# Current_Detection_1_8.net
KiCad netlist of a schematic drawn in Altium Designer
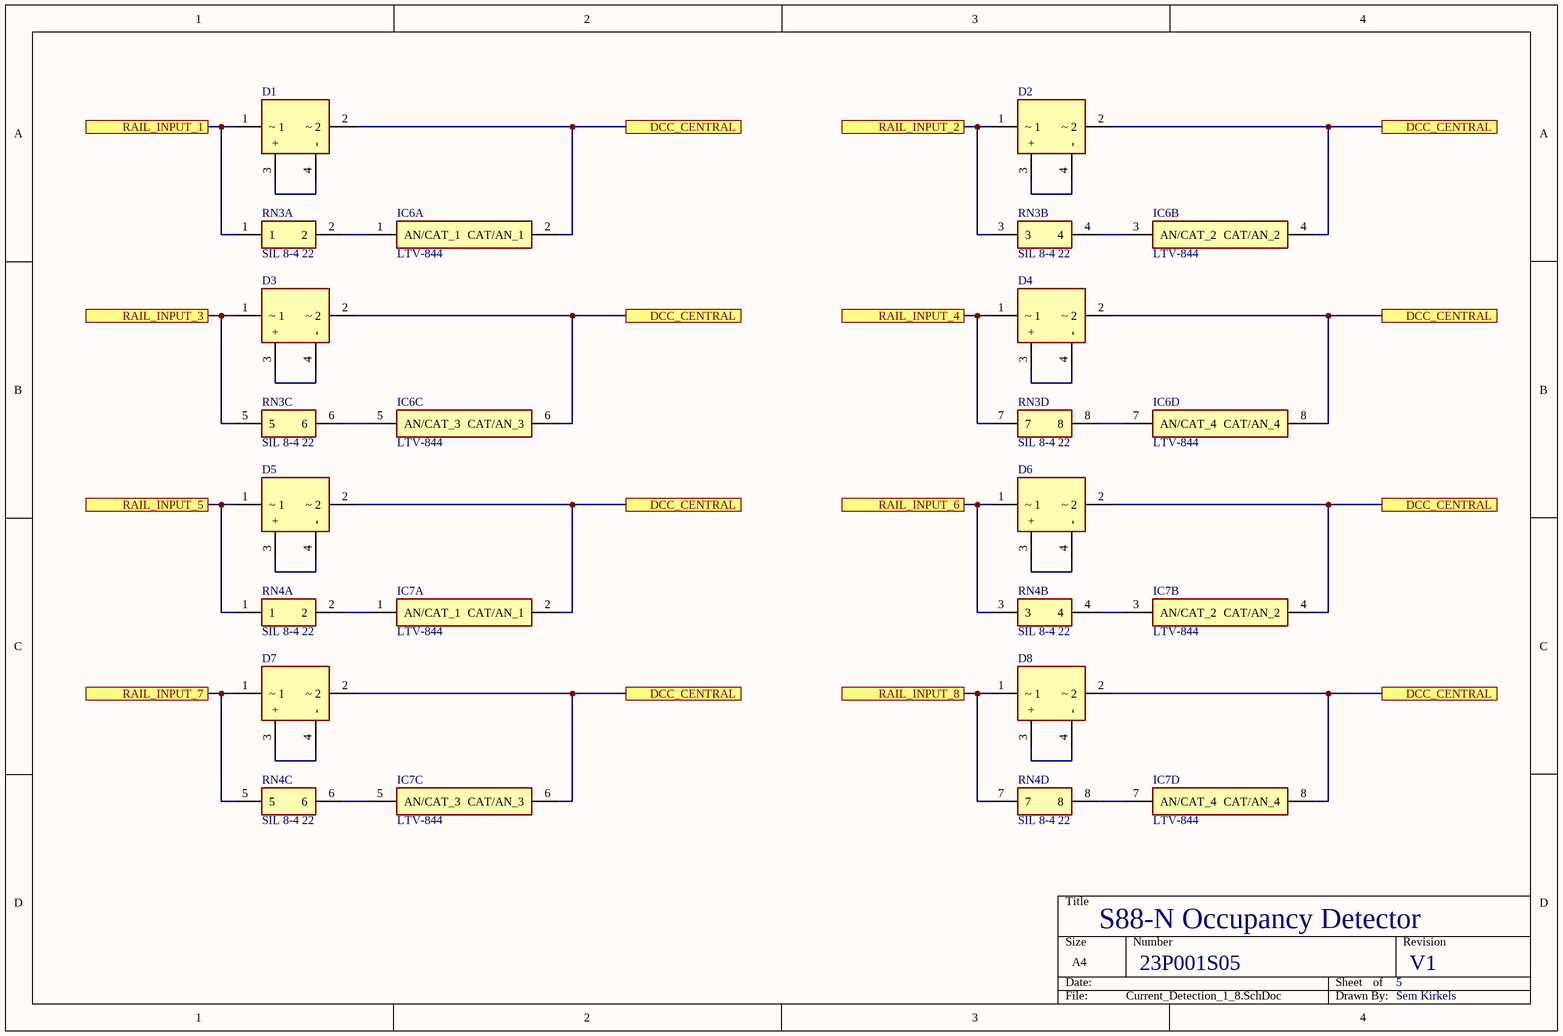
[diagram p0: Current_Detection_1_8.SchDoc]

(export (version "E")
  (design (tool "Eeschema 10.0.6"))
  (components
    (comp (ref "D1")
      (value "B140C1000DIP_DB101")
      (footprint "FBR_B140C1000DIP")
      (description "Bridge Rectifier")
      (fields
        (field (name "MANUFACTURER_PART_NUMBER") "DB101")
        (field (name "MOUSER PART NUMBER") "583-DB101")
      )
      (libsource (lib "Schematic_Library_S88N") (part "B140C1000DIP_DB101"))
    )
    (comp (ref "D2")
      (value "B140C1000DIP_DB101")
      (footprint "FBR_B140C1000DIP")
      (description "Bridge Rectifier")
      (fields
        (field (name "MANUFACTURER_PART_NUMBER") "DB101")
        (field (name "MOUSER PART NUMBER") "583-DB101")
      )
      (libsource (lib "Schematic_Library_S88N") (part "B140C1000DIP_DB101"))
    )
    (comp (ref "D3")
      (value "B140C1000DIP_DB101")
      (footprint "FBR_B140C1000DIP")
      (description "Bridge Rectifier")
      (fields
        (field (name "MANUFACTURER_PART_NUMBER") "DB101")
        (field (name "MOUSER PART NUMBER") "583-DB101")
      )
      (libsource (lib "Schematic_Library_S88N") (part "B140C1000DIP_DB101"))
    )
    (comp (ref "D4")
      (value "B140C1000DIP_DB101")
      (footprint "FBR_B140C1000DIP")
      (description "Bridge Rectifier")
      (fields
        (field (name "MANUFACTURER_PART_NUMBER") "DB101")
        (field (name "MOUSER PART NUMBER") "583-DB101")
      )
      (libsource (lib "Schematic_Library_S88N") (part "B140C1000DIP_DB101"))
    )
    (comp (ref "D5")
      (value "B140C1000DIP_DB101")
      (footprint "FBR_B140C1000DIP")
      (description "Bridge Rectifier")
      (fields
        (field (name "MANUFACTURER_PART_NUMBER") "DB101")
        (field (name "MOUSER PART NUMBER") "583-DB101")
      )
      (libsource (lib "Schematic_Library_S88N") (part "B140C1000DIP_DB101"))
    )
    (comp (ref "D6")
      (value "B140C1000DIP_DB101")
      (footprint "FBR_B140C1000DIP")
      (description "Bridge Rectifier")
      (fields
        (field (name "MANUFACTURER_PART_NUMBER") "DB101")
        (field (name "MOUSER PART NUMBER") "583-DB101")
      )
      (libsource (lib "Schematic_Library_S88N") (part "B140C1000DIP_DB101"))
    )
    (comp (ref "D7")
      (value "B140C1000DIP_DB101")
      (footprint "FBR_B140C1000DIP")
      (description "Bridge Rectifier")
      (fields
        (field (name "MANUFACTURER_PART_NUMBER") "DB101")
        (field (name "MOUSER PART NUMBER") "583-DB101")
      )
      (libsource (lib "Schematic_Library_S88N") (part "B140C1000DIP_DB101"))
    )
    (comp (ref "D8")
      (value "B140C1000DIP_DB101")
      (footprint "FBR_B140C1000DIP")
      (description "Bridge Rectifier")
      (fields
        (field (name "MANUFACTURER_PART_NUMBER") "DB101")
        (field (name "MOUSER PART NUMBER") "583-DB101")
      )
      (libsource (lib "Schematic_Library_S88N") (part "B140C1000DIP_DB101"))
    )
    (comp (ref "IC6")
      (value "LTV-844")
      (footprint "CD4014")
      (description "Integrated Circuit")
      (fields (field (name "MOUSER PART NUMBER") "859-LTV-844"))
      (libsource (lib "Schematic_Library_S88N") (part "LTV-844"))
    )
    (comp (ref "IC7")
      (value "LTV-844")
      (footprint "CD4014")
      (description "Integrated Circuit")
      (fields (field (name "MOUSER PART NUMBER") "859-LTV-844"))
      (libsource (lib "Schematic_Library_S88N") (part "LTV-844"))
    )
    (comp (ref "RN3")
      (value "SIL 8-4 22")
      (footprint "SIL 8-4")
      (description "Resistor Network")
      (fields
        (field (name "MANUFACTURER_PART_NUMBER") "4608X-102-102LF")
        (field (name "MOUSER PART NUMBER") "652-4608X-2LF-1K")
      )
      (libsource (lib "Schematic_Library_S88N") (part "SIL 8-4 22"))
    )
    (comp (ref "RN4")
      (value "SIL 8-4 22")
      (footprint "SIL 8-4")
      (description "Resistor Network")
      (fields
        (field (name "MANUFACTURER_PART_NUMBER") "4608X-102-102LF")
        (field (name "MOUSER PART NUMBER") "652-4608X-2LF-1K")
      )
      (libsource (lib "Schematic_Library_S88N") (part "SIL 8-4 22"))
    )
  )
  (nets
    (net (code "1") (name "/DCC_CENTRAL") (class "Default")
      (node (ref "D1") (pin "2") (pinfunction "~_2_2") (pintype "passive"))
      (node (ref "D2") (pin "2") (pinfunction "~_2_2") (pintype "passive"))
      (node (ref "D3") (pin "2") (pinfunction "~_2_2") (pintype "passive"))
      (node (ref "D4") (pin "2") (pinfunction "~_2_2") (pintype "passive"))
      (node (ref "D5") (pin "2") (pinfunction "~_2_2") (pintype "passive"))
      (node (ref "D6") (pin "2") (pinfunction "~_2_2") (pintype "passive"))
      (node (ref "D7") (pin "2") (pinfunction "~_2_2") (pintype "passive"))
      (node (ref "D8") (pin "2") (pinfunction "~_2_2") (pintype "passive"))
      (node (ref "IC6") (pin "2") (pinfunction "CAT/AN_1_2") (pintype "passive"))
      (node (ref "IC6") (pin "4") (pinfunction "CAT/AN_2_4") (pintype "passive"))
      (node (ref "IC6") (pin "6") (pinfunction "CAT/AN_3_6") (pintype "passive"))
      (node (ref "IC6") (pin "8") (pinfunction "CAT/AN_4_8") (pintype "passive"))
      (node (ref "IC7") (pin "2") (pinfunction "CAT/AN_1_2") (pintype "passive"))
      (node (ref "IC7") (pin "4") (pinfunction "CAT/AN_2_4") (pintype "passive"))
      (node (ref "IC7") (pin "6") (pinfunction "CAT/AN_3_6") (pintype "passive"))
      (node (ref "IC7") (pin "8") (pinfunction "CAT/AN_4_8") (pintype "passive"))
    )
    (net (code "2") (name "/RAIL_INPUT_1") (class "Default")
      (node (ref "D1") (pin "1") (pinfunction "~_1_1") (pintype "passive"))
      (node (ref "RN3") (pin "1") (pinfunction "1_1") (pintype "passive"))
    )
    (net (code "3") (name "/RAIL_INPUT_2") (class "Default")
      (node (ref "D2") (pin "1") (pinfunction "~_1_1") (pintype "passive"))
      (node (ref "RN3") (pin "3") (pinfunction "3_3") (pintype "passive"))
    )
    (net (code "4") (name "/RAIL_INPUT_3") (class "Default")
      (node (ref "D3") (pin "1") (pinfunction "~_1_1") (pintype "passive"))
      (node (ref "RN3") (pin "5") (pinfunction "5_5") (pintype "passive"))
    )
    (net (code "5") (name "/RAIL_INPUT_4") (class "Default")
      (node (ref "D4") (pin "1") (pinfunction "~_1_1") (pintype "passive"))
      (node (ref "RN3") (pin "7") (pinfunction "7_7") (pintype "passive"))
    )
    (net (code "6") (name "/RAIL_INPUT_5") (class "Default")
      (node (ref "D5") (pin "1") (pinfunction "~_1_1") (pintype "passive"))
      (node (ref "RN4") (pin "1") (pinfunction "1_1") (pintype "passive"))
    )
    (net (code "7") (name "/RAIL_INPUT_6") (class "Default")
      (node (ref "D6") (pin "1") (pinfunction "~_1_1") (pintype "passive"))
      (node (ref "RN4") (pin "3") (pinfunction "3_3") (pintype "passive"))
    )
    (net (code "8") (name "/RAIL_INPUT_7") (class "Default")
      (node (ref "D7") (pin "1") (pinfunction "~_1_1") (pintype "passive"))
      (node (ref "RN4") (pin "5") (pinfunction "5_5") (pintype "passive"))
    )
    (net (code "9") (name "/RAIL_INPUT_8") (class "Default")
      (node (ref "D8") (pin "1") (pinfunction "~_1_1") (pintype "passive"))
      (node (ref "RN4") (pin "7") (pinfunction "7_7") (pintype "passive"))
    )
    (net (code "10") (name "Net-(D1-+)") (class "Default")
      (node (ref "D1") (pin "3") (pinfunction "+_3") (pintype "passive"))
      (node (ref "D1") (pin "4") (pinfunction "-_4") (pintype "passive"))
    )
    (net (code "11") (name "Net-(D2-+)") (class "Default")
      (node (ref "D2") (pin "3") (pinfunction "+_3") (pintype "passive"))
      (node (ref "D2") (pin "4") (pinfunction "-_4") (pintype "passive"))
    )
    (net (code "12") (name "Net-(D3-+)") (class "Default")
      (node (ref "D3") (pin "3") (pinfunction "+_3") (pintype "passive"))
      (node (ref "D3") (pin "4") (pinfunction "-_4") (pintype "passive"))
    )
    (net (code "13") (name "Net-(D4-+)") (class "Default")
      (node (ref "D4") (pin "3") (pinfunction "+_3") (pintype "passive"))
      (node (ref "D4") (pin "4") (pinfunction "-_4") (pintype "passive"))
    )
    (net (code "14") (name "Net-(D5-+)") (class "Default")
      (node (ref "D5") (pin "3") (pinfunction "+_3") (pintype "passive"))
      (node (ref "D5") (pin "4") (pinfunction "-_4") (pintype "passive"))
    )
    (net (code "15") (name "Net-(D6-+)") (class "Default")
      (node (ref "D6") (pin "3") (pinfunction "+_3") (pintype "passive"))
      (node (ref "D6") (pin "4") (pinfunction "-_4") (pintype "passive"))
    )
    (net (code "16") (name "Net-(D7-+)") (class "Default")
      (node (ref "D7") (pin "3") (pinfunction "+_3") (pintype "passive"))
      (node (ref "D7") (pin "4") (pinfunction "-_4") (pintype "passive"))
    )
    (net (code "17") (name "Net-(D8-+)") (class "Default")
      (node (ref "D8") (pin "3") (pinfunction "+_3") (pintype "passive"))
      (node (ref "D8") (pin "4") (pinfunction "-_4") (pintype "passive"))
    )
    (net (code "18") (name "Net-(IC6A-AN{slash}CAT_1)") (class "Default")
      (node (ref "IC6") (pin "1") (pinfunction "AN/CAT_1_1") (pintype "passive"))
      (node (ref "RN3") (pin "2") (pinfunction "2_2") (pintype "passive"))
    )
    (net (code "19") (name "Net-(IC6B-AN{slash}CAT_2)") (class "Default")
      (node (ref "IC6") (pin "3") (pinfunction "AN/CAT_2_3") (pintype "passive"))
      (node (ref "RN3") (pin "4") (pinfunction "4_4") (pintype "passive"))
    )
    (net (code "20") (name "Net-(IC6C-AN{slash}CAT_3)") (class "Default")
      (node (ref "IC6") (pin "5") (pinfunction "AN/CAT_3_5") (pintype "passive"))
      (node (ref "RN3") (pin "6") (pinfunction "6_6") (pintype "passive"))
    )
    (net (code "21") (name "Net-(IC6D-AN{slash}CAT_4)") (class "Default")
      (node (ref "IC6") (pin "7") (pinfunction "AN/CAT_4_7") (pintype "passive"))
      (node (ref "RN3") (pin "8") (pinfunction "8_8") (pintype "passive"))
    )
    (net (code "22") (name "Net-(IC7A-AN{slash}CAT_1)") (class "Default")
      (node (ref "IC7") (pin "1") (pinfunction "AN/CAT_1_1") (pintype "passive"))
      (node (ref "RN4") (pin "2") (pinfunction "2_2") (pintype "passive"))
    )
    (net (code "23") (name "Net-(IC7B-AN{slash}CAT_2)") (class "Default")
      (node (ref "IC7") (pin "3") (pinfunction "AN/CAT_2_3") (pintype "passive"))
      (node (ref "RN4") (pin "4") (pinfunction "4_4") (pintype "passive"))
    )
    (net (code "24") (name "Net-(IC7C-AN{slash}CAT_3)") (class "Default")
      (node (ref "IC7") (pin "5") (pinfunction "AN/CAT_3_5") (pintype "passive"))
      (node (ref "RN4") (pin "6") (pinfunction "6_6") (pintype "passive"))
    )
    (net (code "25") (name "Net-(IC7D-AN{slash}CAT_4)") (class "Default")
      (node (ref "IC7") (pin "7") (pinfunction "AN/CAT_4_7") (pintype "passive"))
      (node (ref "RN4") (pin "8") (pinfunction "8_8") (pintype "passive"))
    )
  )
)
